# df2_redraw.net
KiCad netlist of a schematic drawn in EAGLE
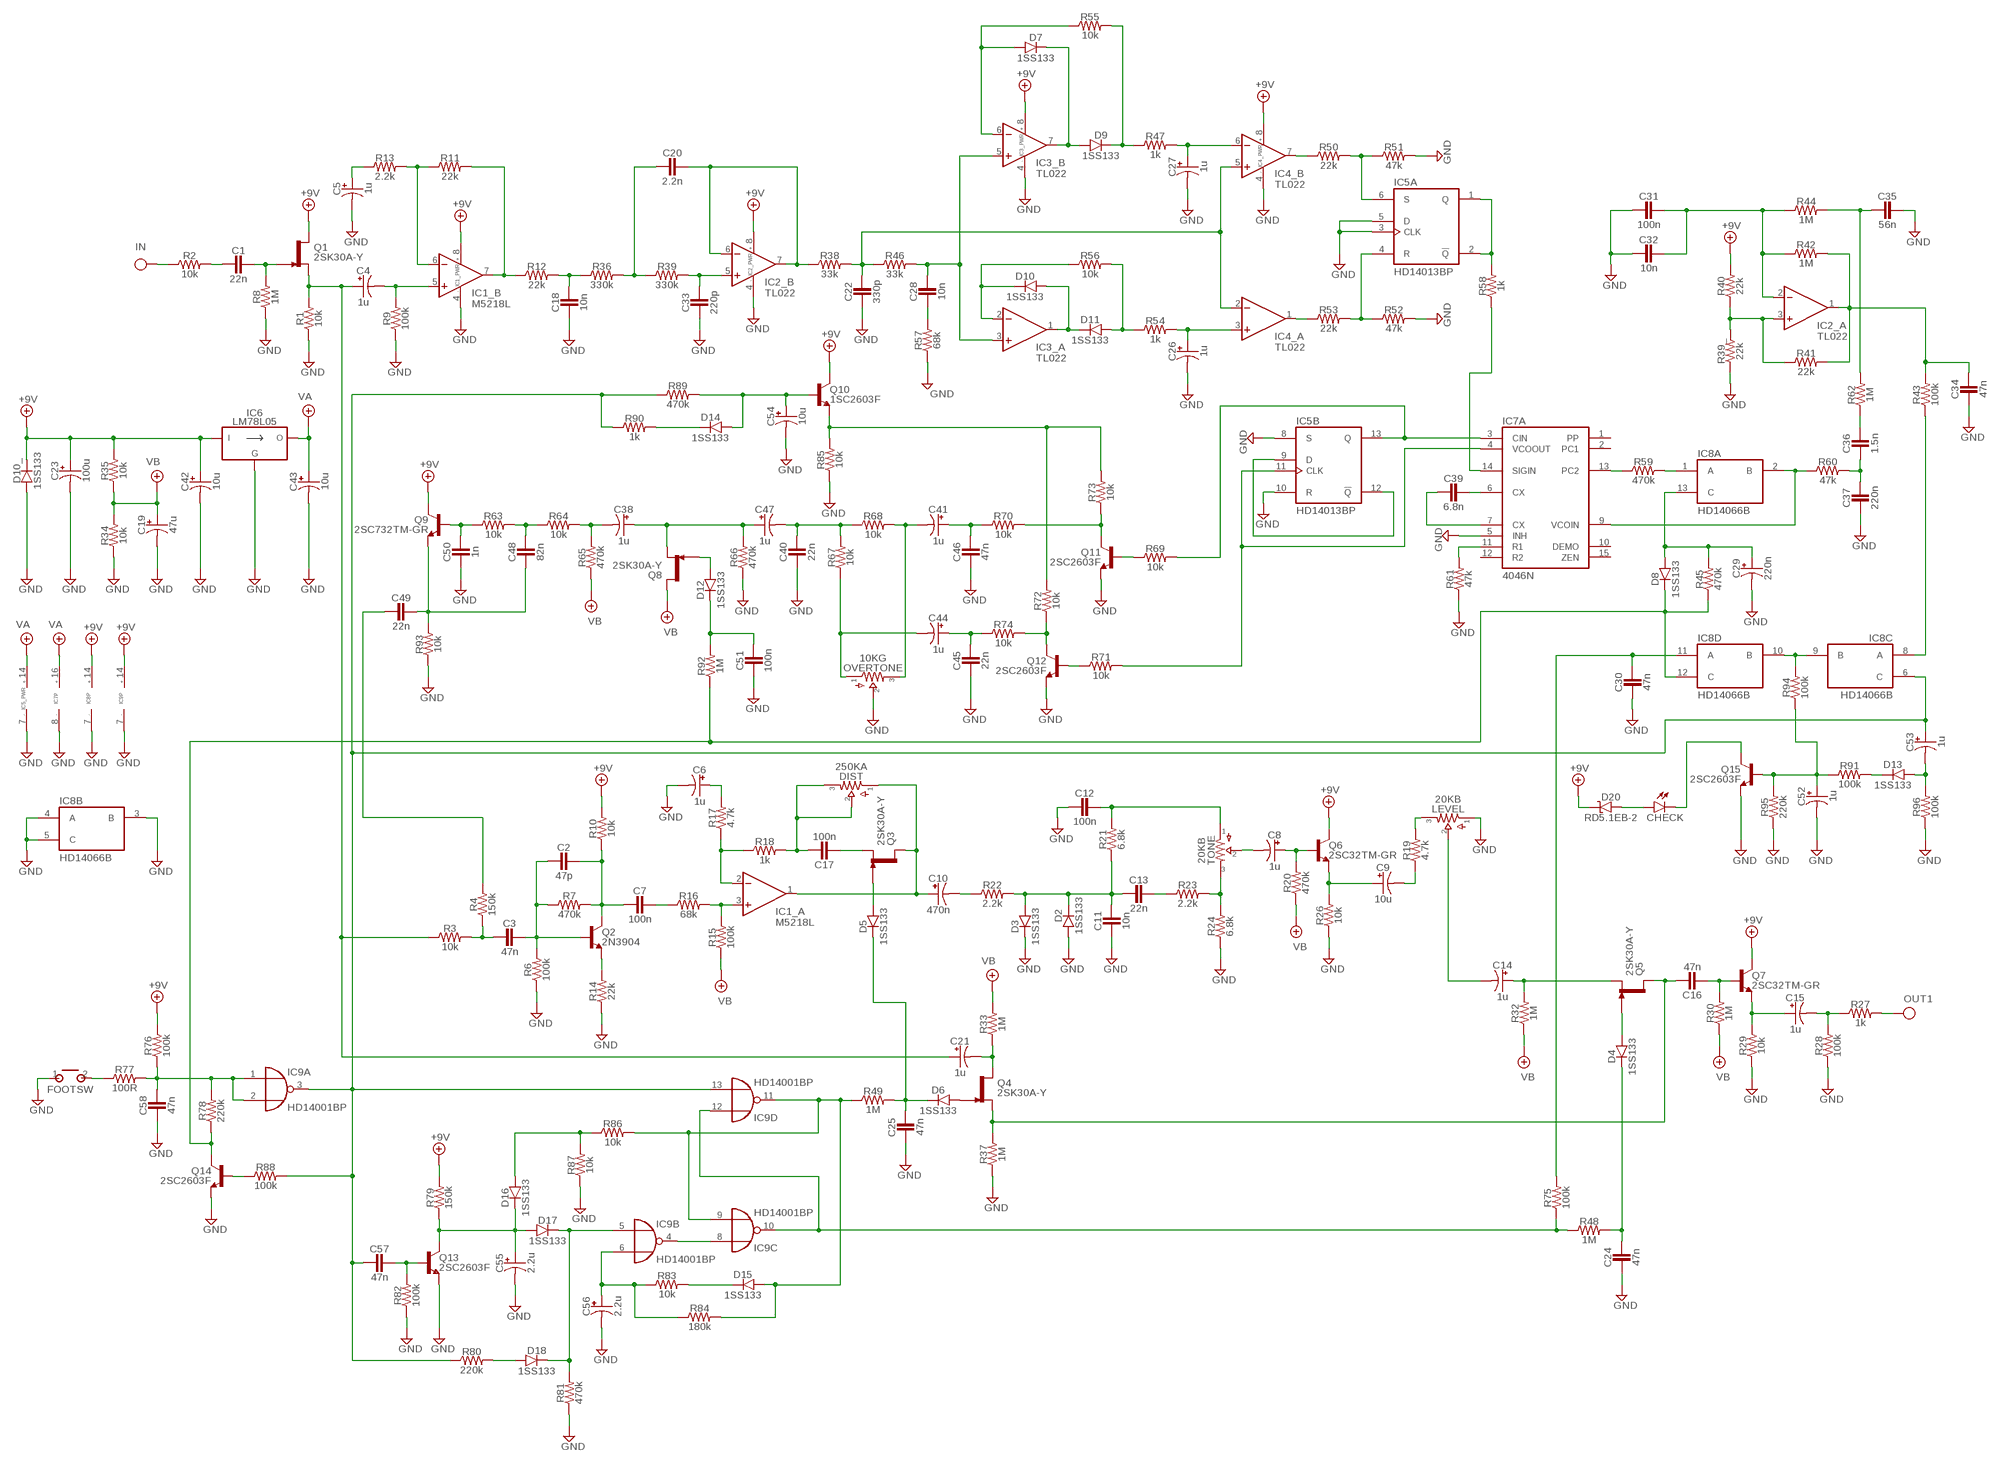
[diagram p0: schematic, sheet 1]

(export (version "E")
  (design (tool "Eeschema 10.0.6"))
  (components
    (comp (ref "C1")
      (value "22n")
      (footprint "eagle-import:BOX_SMALL")
      (libsource (lib "eagle-import") (part "CER/FILMBOX.1"))
    )
    (comp (ref "C2")
      (value "47p")
      (footprint "eagle-import:BOX_SMALL")
      (libsource (lib "eagle-import") (part "CER/FILMBOX.1"))
    )
    (comp (ref "C3")
      (value "47n")
      (footprint "eagle-import:BOX_SMALL")
      (libsource (lib "eagle-import") (part "CER/FILMBOX.1"))
    )
    (comp (ref "C4")
      (value "1u")
      (footprint "eagle-import:040_020")
      (libsource (lib "eagle-import") (part "0400"))
    )
    (comp (ref "C5")
      (value "1u")
      (footprint "eagle-import:040_020")
      (libsource (lib "eagle-import") (part "0400"))
    )
    (comp (ref "C6")
      (value "1u")
      (footprint "eagle-import:040_020")
      (libsource (lib "eagle-import") (part "0400"))
    )
    (comp (ref "C7")
      (value "100n")
      (footprint "eagle-import:BOX_SMALL")
      (libsource (lib "eagle-import") (part "CER/FILMBOX.1"))
    )
    (comp (ref "C8")
      (value "1u")
      (footprint "eagle-import:040_020")
      (libsource (lib "eagle-import") (part "0400"))
    )
    (comp (ref "C9")
      (value "10u")
      (footprint "eagle-import:040_020")
      (libsource (lib "eagle-import") (part "0400"))
    )
    (comp (ref "C10")
      (value "470n")
      (footprint "eagle-import:040_020")
      (libsource (lib "eagle-import") (part "0400"))
    )
    (comp (ref "C11")
      (value "10n")
      (footprint "eagle-import:BOX_SMALL")
      (libsource (lib "eagle-import") (part "CER/FILMBOX.1"))
    )
    (comp (ref "C12")
      (value "100n")
      (footprint "eagle-import:BOX_SMALL")
      (libsource (lib "eagle-import") (part "CER/FILMBOX.1"))
    )
    (comp (ref "C13")
      (value "22n")
      (footprint "eagle-import:BOX_SMALL")
      (libsource (lib "eagle-import") (part "CER/FILMBOX.1"))
    )
    (comp (ref "C14")
      (value "1u")
      (footprint "eagle-import:040_020")
      (libsource (lib "eagle-import") (part "0400"))
    )
    (comp (ref "C15")
      (value "1u")
      (footprint "eagle-import:040_020")
      (libsource (lib "eagle-import") (part "0400"))
    )
    (comp (ref "C16")
      (value "47n")
      (footprint "eagle-import:BOX_SMALL")
      (libsource (lib "eagle-import") (part "CER/FILMBOX.1"))
    )
    (comp (ref "C17")
      (value "100n")
      (footprint "eagle-import:BOX_SMALL")
      (libsource (lib "eagle-import") (part "CER/FILMBOX.1"))
    )
    (comp (ref "C18")
      (value "10n")
      (footprint "eagle-import:BOX_SMALL")
      (libsource (lib "eagle-import") (part "CER/FILMBOX.1"))
    )
    (comp (ref "C19")
      (value "47u")
      (footprint "eagle-import:040_020")
      (libsource (lib "eagle-import") (part "0400"))
    )
    (comp (ref "C20")
      (value "2.2n")
      (footprint "eagle-import:BOX_SMALL")
      (libsource (lib "eagle-import") (part "CER/FILMBOX.1"))
    )
    (comp (ref "C21")
      (value "1u")
      (footprint "eagle-import:040_020")
      (libsource (lib "eagle-import") (part "0400"))
    )
    (comp (ref "C22")
      (value "330p")
      (footprint "eagle-import:BOX_SMALL")
      (libsource (lib "eagle-import") (part "CER/FILMBOX.1"))
    )
    (comp (ref "C23")
      (value "100u")
      (footprint "eagle-import:040_020")
      (libsource (lib "eagle-import") (part "0400"))
    )
    (comp (ref "C24")
      (value "47n")
      (footprint "eagle-import:BOX_SMALL")
      (libsource (lib "eagle-import") (part "CER/FILMBOX.1"))
    )
    (comp (ref "C25")
      (value "47n")
      (footprint "eagle-import:BOX_SMALL")
      (libsource (lib "eagle-import") (part "CER/FILMBOX.1"))
    )
    (comp (ref "C26")
      (value "1u")
      (footprint "eagle-import:040_020")
      (libsource (lib "eagle-import") (part "0400"))
    )
    (comp (ref "C27")
      (value "1u")
      (footprint "eagle-import:040_020")
      (libsource (lib "eagle-import") (part "0400"))
    )
    (comp (ref "C28")
      (value "10n")
      (footprint "eagle-import:BOX_SMALL")
      (libsource (lib "eagle-import") (part "CER/FILMBOX.1"))
    )
    (comp (ref "C29")
      (value "220n")
      (footprint "eagle-import:040_020")
      (libsource (lib "eagle-import") (part "0400"))
    )
    (comp (ref "C30")
      (value "47n")
      (footprint "eagle-import:BOX_SMALL")
      (libsource (lib "eagle-import") (part "CER/FILMBOX.1"))
    )
    (comp (ref "C31")
      (value "100n")
      (footprint "eagle-import:BOX_SMALL")
      (libsource (lib "eagle-import") (part "CER/FILMBOX.1"))
    )
    (comp (ref "C32")
      (value "10n")
      (footprint "eagle-import:BOX_SMALL")
      (libsource (lib "eagle-import") (part "CER/FILMBOX.1"))
    )
    (comp (ref "C33")
      (value "220p")
      (footprint "eagle-import:BOX_SMALL")
      (libsource (lib "eagle-import") (part "CER/FILMBOX.1"))
    )
    (comp (ref "C34")
      (value "47n")
      (footprint "eagle-import:BOX_SMALL")
      (libsource (lib "eagle-import") (part "CER/FILMBOX.1"))
    )
    (comp (ref "C35")
      (value "56n")
      (footprint "eagle-import:BOX_SMALL")
      (libsource (lib "eagle-import") (part "CER/FILMBOX.1"))
    )
    (comp (ref "C36")
      (value "1.5n")
      (footprint "eagle-import:BOX_SMALL")
      (libsource (lib "eagle-import") (part "CER/FILMBOX.1"))
    )
    (comp (ref "C37")
      (value "220n")
      (footprint "eagle-import:BOX_SMALL")
      (libsource (lib "eagle-import") (part "CER/FILMBOX.1"))
    )
    (comp (ref "C38")
      (value "1u")
      (footprint "eagle-import:040_020")
      (libsource (lib "eagle-import") (part "0400"))
    )
    (comp (ref "C39")
      (value "6.8n")
      (footprint "eagle-import:BOX_SMALL")
      (libsource (lib "eagle-import") (part "CER/FILMBOX.1"))
    )
    (comp (ref "C40")
      (value "22n")
      (footprint "eagle-import:BOX_SMALL")
      (libsource (lib "eagle-import") (part "CER/FILMBOX.1"))
    )
    (comp (ref "C41")
      (value "1u")
      (footprint "eagle-import:040_020")
      (libsource (lib "eagle-import") (part "0400"))
    )
    (comp (ref "C42")
      (value "10u")
      (footprint "eagle-import:040_020")
      (libsource (lib "eagle-import") (part "0400"))
    )
    (comp (ref "C43")
      (value "10u")
      (footprint "eagle-import:040_020")
      (libsource (lib "eagle-import") (part "0400"))
    )
    (comp (ref "C44")
      (value "1u")
      (footprint "eagle-import:040_020")
      (libsource (lib "eagle-import") (part "0400"))
    )
    (comp (ref "C45")
      (value "22n")
      (footprint "eagle-import:BOX_SMALL")
      (libsource (lib "eagle-import") (part "CER/FILMBOX.1"))
    )
    (comp (ref "C46")
      (value "47n")
      (footprint "eagle-import:BOX_SMALL")
      (libsource (lib "eagle-import") (part "CER/FILMBOX.1"))
    )
    (comp (ref "C47")
      (value "1u")
      (footprint "eagle-import:040_020")
      (libsource (lib "eagle-import") (part "0400"))
    )
    (comp (ref "C48")
      (value "82n")
      (footprint "eagle-import:BOX_SMALL")
      (libsource (lib "eagle-import") (part "CER/FILMBOX.1"))
    )
    (comp (ref "C49")
      (value "22n")
      (footprint "eagle-import:BOX_SMALL")
      (libsource (lib "eagle-import") (part "CER/FILMBOX.1"))
    )
    (comp (ref "C50")
      (value "1n")
      (footprint "eagle-import:BOX_SMALL")
      (libsource (lib "eagle-import") (part "CER/FILMBOX.1"))
    )
    (comp (ref "C51")
      (value "100n")
      (footprint "eagle-import:BOX_SMALL")
      (libsource (lib "eagle-import") (part "CER/FILMBOX.1"))
    )
    (comp (ref "C52")
      (value "1u")
      (footprint "eagle-import:040_020")
      (libsource (lib "eagle-import") (part "0400"))
    )
    (comp (ref "C53")
      (value "1u")
      (footprint "eagle-import:040_020")
      (libsource (lib "eagle-import") (part "0400"))
    )
    (comp (ref "C54")
      (value "10u")
      (footprint "eagle-import:040_020")
      (libsource (lib "eagle-import") (part "0400"))
    )
    (comp (ref "C55")
      (value "2.2u")
      (footprint "eagle-import:040_020")
      (libsource (lib "eagle-import") (part "0400"))
    )
    (comp (ref "C56")
      (value "2.2u")
      (footprint "eagle-import:040_020")
      (libsource (lib "eagle-import") (part "0400"))
    )
    (comp (ref "C57")
      (value "47n")
      (footprint "eagle-import:BOX_SMALL")
      (libsource (lib "eagle-import") (part "CER/FILMBOX.1"))
    )
    (comp (ref "C58")
      (value "47n")
      (footprint "eagle-import:BOX_SMALL")
      (libsource (lib "eagle-import") (part "CER/FILMBOX.1"))
    )
    (comp (ref "CHECK")
      (value "LED")
      (footprint "eagle-import:3MM_D")
      (libsource (lib "eagle-import") (part "LED"))
    )
    (comp (ref "D2")
      (value "1SS133")
      (footprint "eagle-import:DO35-2")
      (libsource (lib "eagle-import") (part "DO35.2"))
    )
    (comp (ref "D3")
      (value "1SS133")
      (footprint "eagle-import:DO35-2")
      (libsource (lib "eagle-import") (part "DO35.2"))
    )
    (comp (ref "D4")
      (value "1SS133")
      (footprint "eagle-import:DO35-2")
      (libsource (lib "eagle-import") (part "DO35.2"))
    )
    (comp (ref "D5")
      (value "1SS133")
      (footprint "eagle-import:DO35-2")
      (libsource (lib "eagle-import") (part "DO35.2"))
    )
    (comp (ref "D6")
      (value "1SS133")
      (footprint "eagle-import:DO35-2")
      (libsource (lib "eagle-import") (part "DO35.2"))
    )
    (comp (ref "D7")
      (value "1SS133")
      (footprint "eagle-import:DO35-2")
      (libsource (lib "eagle-import") (part "DO35.2"))
    )
    (comp (ref "D8")
      (value "1SS133")
      (footprint "eagle-import:DO35-2")
      (libsource (lib "eagle-import") (part "DO35.2"))
    )
    (comp (ref "D9")
      (value "1SS133")
      (footprint "eagle-import:DO35-2")
      (libsource (lib "eagle-import") (part "DO35.2"))
    )
    (comp (ref "D10")
      (value "1SS133")
      (footprint "eagle-import:DO35-2")
      (libsource (lib "eagle-import") (part "DO35.2"))
    )
    (comp (ref "D10_")
      (value "1SS133")
      (footprint "eagle-import:DO35-2")
      (libsource (lib "eagle-import") (part "DO35.2"))
    )
    (comp (ref "D11")
      (value "1SS133")
      (footprint "eagle-import:DO35-2")
      (libsource (lib "eagle-import") (part "DO35.2"))
    )
    (comp (ref "D12")
      (value "1SS133")
      (footprint "eagle-import:DO35-2")
      (libsource (lib "eagle-import") (part "DO35.2"))
    )
    (comp (ref "D13")
      (value "1SS133")
      (footprint "eagle-import:DO35-2")
      (libsource (lib "eagle-import") (part "DO35.2"))
    )
    (comp (ref "D14")
      (value "1SS133")
      (footprint "eagle-import:DO35-2")
      (libsource (lib "eagle-import") (part "DO35.2"))
    )
    (comp (ref "D15")
      (value "1SS133")
      (footprint "eagle-import:DO35-2")
      (libsource (lib "eagle-import") (part "DO35.2"))
    )
    (comp (ref "D16")
      (value "1SS133")
      (footprint "eagle-import:DO35-2")
      (libsource (lib "eagle-import") (part "DO35.2"))
    )
    (comp (ref "D17")
      (value "1SS133")
      (footprint "eagle-import:DO35-2")
      (libsource (lib "eagle-import") (part "DO35.2"))
    )
    (comp (ref "D18")
      (value "1SS133")
      (footprint "eagle-import:DO35-2")
      (libsource (lib "eagle-import") (part "DO35.2"))
    )
    (comp (ref "D20")
      (value "RD5.1EB-2")
      (footprint "eagle-import:DO41-2")
      (libsource (lib "eagle-import") (part "ZENER.2"))
    )
    (comp (ref "DIST")
      (value "250KA")
      (footprint "eagle-import:16MM_CENTERMOUNT")
      (libsource (lib "eagle-import") (part "POTS"))
    )
    (comp (ref "FOOTSW")
      (value "MOMENTARY")
      (footprint "eagle-import:SPST")
      (libsource (lib "eagle-import") (part "MOMENTARY"))
    )
    (comp (ref "IC1")
      (value "M5218L")
      (footprint "eagle-import:DIL0")
      (libsource (lib "eagle-import") (part "DUALTH"))
    )
    (comp (ref "IC2")
      (value "TL022")
      (footprint "eagle-import:DIL0")
      (libsource (lib "eagle-import") (part "DUALTH"))
    )
    (comp (ref "IC3")
      (value "TL022")
      (footprint "eagle-import:DIL0")
      (libsource (lib "eagle-import") (part "DUALTH"))
    )
    (comp (ref "IC4")
      (value "TL022")
      (footprint "eagle-import:DIL0")
      (libsource (lib "eagle-import") (part "DUALTH"))
    )
    (comp (ref "IC5")
      (value "HD14013BP")
      (footprint "eagle-import:DIL14")
      (libsource (lib "eagle-import") (part "4013N"))
    )
    (comp (ref "IC6")
      (value "LM78L05")
      (footprint "eagle-import:TO92-")
      (libsource (lib "eagle-import") (part "LM78L05"))
    )
    (comp (ref "IC7")
      (value "4046N")
      (footprint "eagle-import:DIL16")
      (libsource (lib "eagle-import") (part "4046N"))
    )
    (comp (ref "IC8")
      (value "HD14066B")
      (footprint "eagle-import:DIL14")
      (libsource (lib "eagle-import") (part "4066N"))
    )
    (comp (ref "IC9")
      (value "HD14001BP")
      (footprint "eagle-import:DIL14")
      (libsource (lib "eagle-import") (part "4001N"))
    )
    (comp (ref "LEVEL")
      (value "20KB")
      (footprint "eagle-import:16MM_CENTERMOUNT")
      (libsource (lib "eagle-import") (part "POTS"))
    )
    (comp (ref "OVERTONE")
      (value "10KG")
      (footprint "eagle-import:16MM_CENTERMOUNT")
      (libsource (lib "eagle-import") (part "POTS"))
    )
    (comp (ref "Q1")
      (value "2SK30A-Y")
      (footprint "eagle-import:TO92-")
      (libsource (lib "eagle-import") (part "2SK30A"))
    )
    (comp (ref "Q2")
      (value "2N3904")
      (footprint "eagle-import:TO92-")
      (libsource (lib "eagle-import") (part "2N3904"))
    )
    (comp (ref "Q3")
      (value "2SK30A-Y")
      (footprint "eagle-import:TO92-")
      (libsource (lib "eagle-import") (part "2SK30A"))
    )
    (comp (ref "Q4")
      (value "2SK30A-Y")
      (footprint "eagle-import:TO92-")
      (libsource (lib "eagle-import") (part "2SK30A"))
    )
    (comp (ref "Q5")
      (value "2SK30A-Y")
      (footprint "eagle-import:TO92-")
      (libsource (lib "eagle-import") (part "2SK30A"))
    )
    (comp (ref "Q6")
      (value "2SC32TM-GR")
      (footprint "eagle-import:TO92-")
      (libsource (lib "eagle-import") (part "2N3904"))
    )
    (comp (ref "Q7")
      (value "2SC32TM-GR")
      (footprint "eagle-import:TO92-")
      (libsource (lib "eagle-import") (part "2N3904"))
    )
    (comp (ref "Q8")
      (value "2SK30A-Y")
      (footprint "eagle-import:TO92-")
      (libsource (lib "eagle-import") (part "2SK30A"))
    )
    (comp (ref "Q9")
      (value "2SC732TM-GR")
      (footprint "eagle-import:TO92-")
      (libsource (lib "eagle-import") (part "2N3904"))
    )
    (comp (ref "Q10")
      (value "1SC2603F")
      (footprint "eagle-import:TO92-")
      (libsource (lib "eagle-import") (part "2N3904"))
    )
    (comp (ref "Q11")
      (value "2SC2603F")
      (footprint "eagle-import:TO92-")
      (libsource (lib "eagle-import") (part "2N3904"))
    )
    (comp (ref "Q12")
      (value "2SC2603F")
      (footprint "eagle-import:TO92-")
      (libsource (lib "eagle-import") (part "2N3904"))
    )
    (comp (ref "Q13")
      (value "2SC2603F")
      (footprint "eagle-import:TO92-")
      (libsource (lib "eagle-import") (part "2N3904"))
    )
    (comp (ref "Q14")
      (value "2SC2603F")
      (footprint "eagle-import:TO92-")
      (libsource (lib "eagle-import") (part "2N3904"))
    )
    (comp (ref "Q15")
      (value "2SC2603F")
      (footprint "eagle-import:TO92-")
      (libsource (lib "eagle-import") (part "2N3904"))
    )
    (comp (ref "R1")
      (value "10k")
      (footprint "eagle-import:R0207_3")
      (libsource (lib "eagle-import") (part "R_.3B"))
    )
    (comp (ref "R2")
      (value "10k")
      (footprint "eagle-import:R0207_3")
      (libsource (lib "eagle-import") (part "R_.3B"))
    )
    (comp (ref "R3")
      (value "10k")
      (footprint "eagle-import:R0207_3")
      (libsource (lib "eagle-import") (part "R_.3B"))
    )
    (comp (ref "R4")
      (value "150k")
      (footprint "eagle-import:R0207_3")
      (libsource (lib "eagle-import") (part "R_.3B"))
    )
    (comp (ref "R6")
      (value "100k")
      (footprint "eagle-import:R0207_3")
      (libsource (lib "eagle-import") (part "R_.3B"))
    )
    (comp (ref "R7")
      (value "470k")
      (footprint "eagle-import:R0207_3")
      (libsource (lib "eagle-import") (part "R_.3B"))
    )
    (comp (ref "R8")
      (value "1M")
      (footprint "eagle-import:R0207_3")
      (libsource (lib "eagle-import") (part "R_.3B"))
    )
    (comp (ref "R9")
      (value "100k")
      (footprint "eagle-import:R0207_3")
      (libsource (lib "eagle-import") (part "R_.3B"))
    )
    (comp (ref "R10")
      (value "10k")
      (footprint "eagle-import:R0207_3")
      (libsource (lib "eagle-import") (part "R_.3B"))
    )
    (comp (ref "R11")
      (value "22k")
      (footprint "eagle-import:R0207_3")
      (libsource (lib "eagle-import") (part "R_.3B"))
    )
    (comp (ref "R12")
      (value "22k")
      (footprint "eagle-import:R0207_3")
      (libsource (lib "eagle-import") (part "R_.3B"))
    )
    (comp (ref "R13")
      (value "2.2k")
      (footprint "eagle-import:R0207_3")
      (libsource (lib "eagle-import") (part "R_.3B"))
    )
    (comp (ref "R14")
      (value "22k")
      (footprint "eagle-import:R0207_3")
      (libsource (lib "eagle-import") (part "R_.3B"))
    )
    (comp (ref "R15")
      (value "100k")
      (footprint "eagle-import:R0207_3")
      (libsource (lib "eagle-import") (part "R_.3B"))
    )
    (comp (ref "R16")
      (value "68k")
      (footprint "eagle-import:R0207_3")
      (libsource (lib "eagle-import") (part "R_.3B"))
    )
    (comp (ref "R17")
      (value "4.7k")
      (footprint "eagle-import:R0207_3")
      (libsource (lib "eagle-import") (part "R_.3B"))
    )
    (comp (ref "R18")
      (value "1k")
      (footprint "eagle-import:R0207_3")
      (libsource (lib "eagle-import") (part "R_.3B"))
    )
    (comp (ref "R19")
      (value "4.7k")
      (footprint "eagle-import:R0207_3")
      (libsource (lib "eagle-import") (part "R_.3B"))
    )
    (comp (ref "R20")
      (value "470k")
      (footprint "eagle-import:R0207_3")
      (libsource (lib "eagle-import") (part "R_.3B"))
    )
    (comp (ref "R21")
      (value "6.8k")
      (footprint "eagle-import:R0207_3")
      (libsource (lib "eagle-import") (part "R_.3B"))
    )
    (comp (ref "R22")
      (value "2.2k")
      (footprint "eagle-import:R0207_3")
      (libsource (lib "eagle-import") (part "R_.3B"))
    )
    (comp (ref "R23")
      (value "2.2k")
      (footprint "eagle-import:R0207_3")
      (libsource (lib "eagle-import") (part "R_.3B"))
    )
    (comp (ref "R24")
      (value "6.8k")
      (footprint "eagle-import:R0207_3")
      (libsource (lib "eagle-import") (part "R_.3B"))
    )
    (comp (ref "R26")
      (value "10k")
      (footprint "eagle-import:R0207_3")
      (libsource (lib "eagle-import") (part "R_.3B"))
    )
    (comp (ref "R27")
      (value "1k")
      (footprint "eagle-import:R0207_3")
      (libsource (lib "eagle-import") (part "R_.3B"))
    )
    (comp (ref "R28")
      (value "100k")
      (footprint "eagle-import:R0207_3")
      (libsource (lib "eagle-import") (part "R_.3B"))
    )
    (comp (ref "R29")
      (value "10k")
      (footprint "eagle-import:R0207_3")
      (libsource (lib "eagle-import") (part "R_.3B"))
    )
    (comp (ref "R30")
      (value "1M")
      (footprint "eagle-import:R0207_3")
      (libsource (lib "eagle-import") (part "R_.3B"))
    )
    (comp (ref "R32")
      (value "1M")
      (footprint "eagle-import:R0207_3")
      (libsource (lib "eagle-import") (part "R_.3B"))
    )
    (comp (ref "R33")
      (value "1M")
      (footprint "eagle-import:R0207_3")
      (libsource (lib "eagle-import") (part "R_.3B"))
    )
    (comp (ref "R34")
      (value "10k")
      (footprint "eagle-import:R0207_3")
      (libsource (lib "eagle-import") (part "R_.3B"))
    )
    (comp (ref "R35")
      (value "10k")
      (footprint "eagle-import:R0207_3")
      (libsource (lib "eagle-import") (part "R_.3B"))
    )
    (comp (ref "R36")
      (value "330k")
      (footprint "eagle-import:R0207_3")
      (libsource (lib "eagle-import") (part "R_.3B"))
    )
    (comp (ref "R37")
      (value "1M")
      (footprint "eagle-import:R0207_3")
      (libsource (lib "eagle-import") (part "R_.3B"))
    )
    (comp (ref "R38")
      (value "33k")
      (footprint "eagle-import:R0207_3")
      (libsource (lib "eagle-import") (part "R_.3B"))
    )
    (comp (ref "R39")
      (value "330k")
      (footprint "eagle-import:R0207_3")
      (libsource (lib "eagle-import") (part "R_.3B"))
    )
    (comp (ref "R39_")
      (value "22k")
      (footprint "eagle-import:R0207_3")
      (libsource (lib "eagle-import") (part "R_.3B"))
    )
    (comp (ref "R40")
      (value "22k")
      (footprint "eagle-import:R0207_3")
      (libsource (lib "eagle-import") (part "R_.3B"))
    )
    (comp (ref "R41")
      (value "22k")
      (footprint "eagle-import:R0207_3")
      (libsource (lib "eagle-import") (part "R_.3B"))
    )
    (comp (ref "R42")
      (value "1M")
      (footprint "eagle-import:R0207_3")
      (libsource (lib "eagle-import") (part "R_.3B"))
    )
    (comp (ref "R43")
      (value "100k")
      (footprint "eagle-import:R0207_3")
      (libsource (lib "eagle-import") (part "R_.3B"))
    )
    (comp (ref "R44")
      (value "1M")
      (footprint "eagle-import:R0207_3")
      (libsource (lib "eagle-import") (part "R_.3B"))
    )
    (comp (ref "R45")
      (value "470k")
      (footprint "eagle-import:R0207_3")
      (libsource (lib "eagle-import") (part "R_.3B"))
    )
    (comp (ref "R46")
      (value "33k")
      (footprint "eagle-import:R0207_3")
      (libsource (lib "eagle-import") (part "R_.3B"))
    )
    (comp (ref "R47")
      (value "1k")
      (footprint "eagle-import:R0207_3")
      (libsource (lib "eagle-import") (part "R_.3B"))
    )
    (comp (ref "R48")
      (value "1M")
      (footprint "eagle-import:R0207_3")
      (libsource (lib "eagle-import") (part "R_.3B"))
    )
    (comp (ref "R49")
      (value "1M")
      (footprint "eagle-import:R0207_3")
      (libsource (lib "eagle-import") (part "R_.3B"))
    )
    (comp (ref "R50")
      (value "22k")
      (footprint "eagle-import:R0207_3")
      (libsource (lib "eagle-import") (part "R_.3B"))
    )
    (comp (ref "R51")
      (value "47k")
      (footprint "eagle-import:R0207_3")
      (libsource (lib "eagle-import") (part "R_.3B"))
    )
    (comp (ref "R52")
      (value "47k")
      (footprint "eagle-import:R0207_3")
      (libsource (lib "eagle-import") (part "R_.3B"))
    )
    (comp (ref "R53")
      (value "22k")
      (footprint "eagle-import:R0207_3")
      (libsource (lib "eagle-import") (part "R_.3B"))
    )
    (comp (ref "R54")
      (value "1k")
      (footprint "eagle-import:R0207_3")
      (libsource (lib "eagle-import") (part "R_.3B"))
    )
    (comp (ref "R55")
      (value "10k")
      (footprint "eagle-import:R0207_3")
      (libsource (lib "eagle-import") (part "R_.3B"))
    )
    (comp (ref "R56")
      (value "10k")
      (footprint "eagle-import:R0207_3")
      (libsource (lib "eagle-import") (part "R_.3B"))
    )
    (comp (ref "R57")
      (value "68k")
      (footprint "eagle-import:R0207_3")
      (libsource (lib "eagle-import") (part "R_.3B"))
    )
    (comp (ref "R58")
      (value "1k")
      (footprint "eagle-import:R0207_3")
      (libsource (lib "eagle-import") (part "R_.3B"))
    )
    (comp (ref "R59")
      (value "470k")
      (footprint "eagle-import:R0207_3")
      (libsource (lib "eagle-import") (part "R_.3B"))
    )
    (comp (ref "R60")
      (value "47k")
      (footprint "eagle-import:R0207_3")
      (libsource (lib "eagle-import") (part "R_.3B"))
    )
    (comp (ref "R61")
      (value "47k")
      (footprint "eagle-import:R0207_3")
      (libsource (lib "eagle-import") (part "R_.3B"))
    )
    (comp (ref "R62")
      (value "1M")
      (footprint "eagle-import:R0207_3")
      (libsource (lib "eagle-import") (part "R_.3B"))
    )
    (comp (ref "R63")
      (value "10k")
      (footprint "eagle-import:R0207_3")
      (libsource (lib "eagle-import") (part "R_.3B"))
    )
    (comp (ref "R64")
      (value "10k")
      (footprint "eagle-import:R0207_3")
      (libsource (lib "eagle-import") (part "R_.3B"))
    )
    (comp (ref "R65")
      (value "470k")
      (footprint "eagle-import:R0207_3")
      (libsource (lib "eagle-import") (part "R_.3B"))
    )
    (comp (ref "R66")
      (value "470k")
      (footprint "eagle-import:R0207_3")
      (libsource (lib "eagle-import") (part "R_.3B"))
    )
    (comp (ref "R67")
      (value "10k")
      (footprint "eagle-import:R0207_3")
      (libsource (lib "eagle-import") (part "R_.3B"))
    )
    (comp (ref "R68")
      (value "10k")
      (footprint "eagle-import:R0207_3")
      (libsource (lib "eagle-import") (part "R_.3B"))
    )
    (comp (ref "R69")
      (value "10k")
      (footprint "eagle-import:R0207_3")
      (libsource (lib "eagle-import") (part "R_.3B"))
    )
    (comp (ref "R70")
      (value "10k")
      (footprint "eagle-import:R0207_3")
      (libsource (lib "eagle-import") (part "R_.3B"))
    )
    (comp (ref "R71")
      (value "10k")
      (footprint "eagle-import:R0207_3")
      (libsource (lib "eagle-import") (part "R_.3B"))
    )
    (comp (ref "R72")
      (value "10k")
      (footprint "eagle-import:R0207_3")
      (libsource (lib "eagle-import") (part "R_.3B"))
    )
    (comp (ref "R73")
      (value "10k")
      (footprint "eagle-import:R0207_3")
      (libsource (lib "eagle-import") (part "R_.3B"))
    )
    (comp (ref "R74")
      (value "10k")
      (footprint "eagle-import:R0207_3")
      (libsource (lib "eagle-import") (part "R_.3B"))
    )
    (comp (ref "R75")
      (value "100k")
      (footprint "eagle-import:R0207_3")
      (libsource (lib "eagle-import") (part "R_.3B"))
    )
    (comp (ref "R76")
      (value "100k")
      (footprint "eagle-import:R0207_3")
      (libsource (lib "eagle-import") (part "R_.3B"))
    )
    (comp (ref "R77")
      (value "100R")
      (footprint "eagle-import:R0207_3")
      (libsource (lib "eagle-import") (part "R_.3B"))
    )
    (comp (ref "R78")
      (value "220k")
      (footprint "eagle-import:R0207_3")
      (libsource (lib "eagle-import") (part "R_.3B"))
    )
    (comp (ref "R79")
      (value "150k")
      (footprint "eagle-import:R0207_3")
      (libsource (lib "eagle-import") (part "R_.3B"))
    )
    (comp (ref "R80")
      (value "220k")
      (footprint "eagle-import:R0207_3")
      (libsource (lib "eagle-import") (part "R_.3B"))
    )
    (comp (ref "R81")
      (value "470k")
      (footprint "eagle-import:R0207_3")
      (libsource (lib "eagle-import") (part "R_.3B"))
    )
    (comp (ref "R82")
      (value "100k")
      (footprint "eagle-import:R0207_3")
      (libsource (lib "eagle-import") (part "R_.3B"))
    )
    (comp (ref "R83")
      (value "10k")
      (footprint "eagle-import:R0207_3")
      (libsource (lib "eagle-import") (part "R_.3B"))
    )
    (comp (ref "R84")
      (value "180k")
      (footprint "eagle-import:R0207_3")
      (libsource (lib "eagle-import") (part "R_.3B"))
    )
    (comp (ref "R85")
      (value "10k")
      (footprint "eagle-import:R0207_3")
      (libsource (lib "eagle-import") (part "R_.3B"))
    )
    (comp (ref "R86")
      (value "10k")
      (footprint "eagle-import:R0207_3")
      (libsource (lib "eagle-import") (part "R_.3B"))
    )
    (comp (ref "R87")
      (value "10k")
      (footprint "eagle-import:R0207_3")
      (libsource (lib "eagle-import") (part "R_.3B"))
    )
    (comp (ref "R88")
      (value "100k")
      (footprint "eagle-import:R0207_3")
      (libsource (lib "eagle-import") (part "R_.3B"))
    )
    (comp (ref "R89")
      (value "470k")
      (footprint "eagle-import:R0207_3")
      (libsource (lib "eagle-import") (part "R_.3B"))
    )
    (comp (ref "R90")
      (value "1k")
      (footprint "eagle-import:R0207_3")
      (libsource (lib "eagle-import") (part "R_.3B"))
    )
    (comp (ref "R91")
      (value "100k")
      (footprint "eagle-import:R0207_3")
      (libsource (lib "eagle-import") (part "R_.3B"))
    )
    (comp (ref "R92")
      (value "1M")
      (footprint "eagle-import:R0207_3")
      (libsource (lib "eagle-import") (part "R_.3B"))
    )
    (comp (ref "R93")
      (value "10k")
      (footprint "eagle-import:R0207_3")
      (libsource (lib "eagle-import") (part "R_.3B"))
    )
    (comp (ref "R94")
      (value "100k")
      (footprint "eagle-import:R0207_3")
      (libsource (lib "eagle-import") (part "R_.3B"))
    )
    (comp (ref "R95")
      (value "220k")
      (footprint "eagle-import:R0207_3")
      (libsource (lib "eagle-import") (part "R_.3B"))
    )
    (comp (ref "R96")
      (value "100k")
      (footprint "eagle-import:R0207_3")
      (libsource (lib "eagle-import") (part "R_.3B"))
    )
    (comp (ref "TONE")
      (value "20KB")
      (footprint "eagle-import:16MM_CENTERMOUNT")
      (libsource (lib "eagle-import") (part "POTS"))
    )
  )
  (nets
    (net (code "1") (name "+9V") (class "Default")
      (node (ref "C23") (pin "+") (pinfunction "+_+") (pintype "passive"))
      (node (ref "C42") (pin "+") (pinfunction "+_+") (pintype "passive"))
      (node (ref "D10_") (pin "C") (pinfunction "C_C") (pintype "passive"))
      (node (ref "D20") (pin "C") (pinfunction "C_C") (pintype "passive"))
      (node (ref "IC1") (pin "8") (pinfunction "V+_8") (pintype "power_in"))
      (node (ref "IC2") (pin "8") (pinfunction "V+_8") (pintype "power_in"))
      (node (ref "IC3") (pin "8") (pinfunction "V+_8") (pintype "power_in"))
      (node (ref "IC4") (pin "8") (pinfunction "V+_8") (pintype "power_in"))
      (node (ref "IC6") (pin "1") (pinfunction "VI_1") (pintype "input"))
      (node (ref "IC8") (pin "14") (pinfunction "VDD_14") (pintype "power_in"))
      (node (ref "IC9") (pin "14") (pinfunction "VDD_14") (pintype "power_in"))
      (node (ref "Q1") (pin "1") (pinfunction "D_1") (pintype "passive"))
      (node (ref "Q10") (pin "1") (pinfunction "C_1") (pintype "passive"))
      (node (ref "Q6") (pin "1") (pinfunction "C_1") (pintype "passive"))
      (node (ref "Q7") (pin "1") (pinfunction "C_1") (pintype "passive"))
      (node (ref "Q9") (pin "1") (pinfunction "C_1") (pintype "passive"))
      (node (ref "R10") (pin "2") (pinfunction "2_2") (pintype "passive"))
      (node (ref "R35") (pin "2") (pinfunction "2_2") (pintype "passive"))
      (node (ref "R40") (pin "2") (pinfunction "2_2") (pintype "passive"))
      (node (ref "R76") (pin "2") (pinfunction "2_2") (pintype "passive"))
      (node (ref "R79") (pin "2") (pinfunction "2_2") (pintype "passive"))
    )
    (net (code "2") (name "GND") (class "Default")
      (node (ref "C11") (pin "2") (pinfunction "2_2") (pintype "passive"))
      (node (ref "C12") (pin "2") (pinfunction "2_2") (pintype "passive"))
      (node (ref "C18") (pin "2") (pinfunction "2_2") (pintype "passive"))
      (node (ref "C19") (pin "-") (pinfunction "-_-") (pintype "passive"))
      (node (ref "C22") (pin "2") (pinfunction "2_2") (pintype "passive"))
      (node (ref "C23") (pin "-") (pinfunction "-_-") (pintype "passive"))
      (node (ref "C24") (pin "2") (pinfunction "2_2") (pintype "passive"))
      (node (ref "C25") (pin "2") (pinfunction "2_2") (pintype "passive"))
      (node (ref "C26") (pin "-") (pinfunction "-_-") (pintype "passive"))
      (node (ref "C27") (pin "-") (pinfunction "-_-") (pintype "passive"))
      (node (ref "C29") (pin "-") (pinfunction "-_-") (pintype "passive"))
      (node (ref "C30") (pin "2") (pinfunction "2_2") (pintype "passive"))
      (node (ref "C31") (pin "2") (pinfunction "2_2") (pintype "passive"))
      (node (ref "C32") (pin "2") (pinfunction "2_2") (pintype "passive"))
      (node (ref "C33") (pin "2") (pinfunction "2_2") (pintype "passive"))
      (node (ref "C34") (pin "2") (pinfunction "2_2") (pintype "passive"))
      (node (ref "C35") (pin "1") (pinfunction "1_1") (pintype "passive"))
      (node (ref "C37") (pin "2") (pinfunction "2_2") (pintype "passive"))
      (node (ref "C40") (pin "2") (pinfunction "2_2") (pintype "passive"))
      (node (ref "C42") (pin "-") (pinfunction "-_-") (pintype "passive"))
      (node (ref "C43") (pin "-") (pinfunction "-_-") (pintype "passive"))
      (node (ref "C45") (pin "2") (pinfunction "2_2") (pintype "passive"))
      (node (ref "C46") (pin "2") (pinfunction "2_2") (pintype "passive"))
      (node (ref "C5") (pin "-") (pinfunction "-_-") (pintype "passive"))
      (node (ref "C50") (pin "2") (pinfunction "2_2") (pintype "passive"))
      (node (ref "C51") (pin "2") (pinfunction "2_2") (pintype "passive"))
      (node (ref "C52") (pin "-") (pinfunction "-_-") (pintype "passive"))
      (node (ref "C54") (pin "-") (pinfunction "-_-") (pintype "passive"))
      (node (ref "C55") (pin "-") (pinfunction "-_-") (pintype "passive"))
      (node (ref "C56") (pin "-") (pinfunction "-_-") (pintype "passive"))
      (node (ref "C58") (pin "2") (pinfunction "2_2") (pintype "passive"))
      (node (ref "C6") (pin "-") (pinfunction "-_-") (pintype "passive"))
      (node (ref "D10_") (pin "A") (pinfunction "A_A") (pintype "passive"))
      (node (ref "D2") (pin "A") (pinfunction "A_A") (pintype "passive"))
      (node (ref "D3") (pin "C") (pinfunction "C_C") (pintype "passive"))
      (node (ref "FOOTSW") (pin "1") (pinfunction "P_1") (pintype "passive"))
      (node (ref "IC1") (pin "4") (pinfunction "V-_4") (pintype "power_in"))
      (node (ref "IC2") (pin "4") (pinfunction "V-_4") (pintype "power_in"))
      (node (ref "IC3") (pin "4") (pinfunction "V-_4") (pintype "power_in"))
      (node (ref "IC4") (pin "4") (pinfunction "V-_4") (pintype "power_in"))
      (node (ref "IC5") (pin "10") (pinfunction "R_10") (pintype "input"))
      (node (ref "IC5") (pin "3") (pinfunction "CLK_3") (pintype "input"))
      (node (ref "IC5") (pin "5") (pinfunction "D_5") (pintype "input"))
      (node (ref "IC5") (pin "7") (pinfunction "VSS_7") (pintype "power_in"))
      (node (ref "IC5") (pin "8") (pinfunction "S_8") (pintype "input"))
      (node (ref "IC6") (pin "2") (pinfunction "GND_2") (pintype "passive"))
      (node (ref "IC7") (pin "5") (pinfunction "INH_5") (pintype "input"))
      (node (ref "IC7") (pin "8") (pinfunction "VSS_8") (pintype "power_in"))
      (node (ref "IC8") (pin "3") (pinfunction "B_3") (pintype "tri_state"))
      (node (ref "IC8") (pin "4") (pinfunction "A_4") (pintype "tri_state"))
      (node (ref "IC8") (pin "5") (pinfunction "C_5") (pintype "input"))
      (node (ref "IC8") (pin "7") (pinfunction "VSS_7") (pintype "power_in"))
      (node (ref "IC9") (pin "7") (pinfunction "VSS_7") (pintype "power_in"))
      (node (ref "LEVEL") (pin "1") (pinfunction "1_1") (pintype "passive"))
      (node (ref "OVERTONE") (pin "2") (pinfunction "2_2") (pintype "passive"))
      (node (ref "Q11") (pin "3") (pinfunction "E_3") (pintype "passive"))
      (node (ref "Q12") (pin "3") (pinfunction "E_3") (pintype "passive"))
      (node (ref "Q13") (pin "3") (pinfunction "E_3") (pintype "passive"))
      (node (ref "Q14") (pin "3") (pinfunction "E_3") (pintype "passive"))
      (node (ref "Q15") (pin "3") (pinfunction "E_3") (pintype "passive"))
      (node (ref "R1") (pin "1") (pinfunction "1_1") (pintype "passive"))
      (node (ref "R14") (pin "1") (pinfunction "1_1") (pintype "passive"))
      (node (ref "R24") (pin "1") (pinfunction "1_1") (pintype "passive"))
      (node (ref "R26") (pin "1") (pinfunction "1_1") (pintype "passive"))
      (node (ref "R28") (pin "1") (pinfunction "1_1") (pintype "passive"))
      (node (ref "R29") (pin "1") (pinfunction "1_1") (pintype "passive"))
      (node (ref "R34") (pin "1") (pinfunction "1_1") (pintype "passive"))
      (node (ref "R37") (pin "1") (pinfunction "1_1") (pintype "passive"))
      (node (ref "R39_") (pin "1") (pinfunction "1_1") (pintype "passive"))
      (node (ref "R51") (pin "2") (pinfunction "2_2") (pintype "passive"))
      (node (ref "R52") (pin "2") (pinfunction "2_2") (pintype "passive"))
      (node (ref "R57") (pin "1") (pinfunction "1_1") (pintype "passive"))
      (node (ref "R6") (pin "1") (pinfunction "1_1") (pintype "passive"))
      (node (ref "R61") (pin "1") (pinfunction "1_1") (pintype "passive"))
      (node (ref "R66") (pin "1") (pinfunction "1_1") (pintype "passive"))
      (node (ref "R8") (pin "1") (pinfunction "1_1") (pintype "passive"))
      (node (ref "R81") (pin "1") (pinfunction "1_1") (pintype "passive"))
      (node (ref "R82") (pin "1") (pinfunction "1_1") (pintype "passive"))
      (node (ref "R85") (pin "1") (pinfunction "1_1") (pintype "passive"))
      (node (ref "R87") (pin "1") (pinfunction "1_1") (pintype "passive"))
      (node (ref "R9") (pin "1") (pinfunction "1_1") (pintype "passive"))
      (node (ref "R93") (pin "1") (pinfunction "1_1") (pintype "passive"))
      (node (ref "R95") (pin "1") (pinfunction "1_1") (pintype "passive"))
      (node (ref "R96") (pin "1") (pinfunction "1_1") (pintype "passive"))
    )
    (net (code "3") (name "IN") (class "Default")
      (node (ref "R2") (pin "1") (pinfunction "1_1") (pintype "passive"))
    )
    (net (code "4") (name "Net-(C1-Pad2)") (class "Default")
      (node (ref "C1") (pin "2") (pinfunction "2_2") (pintype "passive"))
      (node (ref "R2") (pin "2") (pinfunction "2_2") (pintype "passive"))
    )
    (net (code "5") (name "Net-(C3-Pad2)") (class "Default")
      (node (ref "C3") (pin "2") (pinfunction "2_2") (pintype "passive"))
      (node (ref "R3") (pin "2") (pinfunction "2_2") (pintype "passive"))
      (node (ref "R4") (pin "1") (pinfunction "1_1") (pintype "passive"))
    )
    (net (code "6") (name "Net-(C5-Pad+)") (class "Default")
      (node (ref "C5") (pin "+") (pinfunction "+_+") (pintype "passive"))
      (node (ref "R13") (pin "1") (pinfunction "1_1") (pintype "passive"))
    )
    (net (code "7") (name "Net-(C6-Pad+)") (class "Default")
      (node (ref "C6") (pin "+") (pinfunction "+_+") (pintype "passive"))
      (node (ref "R17") (pin "2") (pinfunction "2_2") (pintype "passive"))
    )
    (net (code "8") (name "Net-(C7-Pad1)") (class "Default")
      (node (ref "C7") (pin "1") (pinfunction "1_1") (pintype "passive"))
      (node (ref "R16") (pin "1") (pinfunction "1_1") (pintype "passive"))
    )
    (net (code "9") (name "Net-(C8-Pad-)") (class "Default")
      (node (ref "C8") (pin "-") (pinfunction "-_-") (pintype "passive"))
      (node (ref "TONE") (pin "2") (pinfunction "2_2") (pintype "passive"))
    )
    (net (code "10") (name "Net-(C9-Pad-)") (class "Default")
      (node (ref "C9") (pin "-") (pinfunction "-_-") (pintype "passive"))
      (node (ref "R19") (pin "1") (pinfunction "1_1") (pintype "passive"))
    )
    (net (code "11") (name "Net-(C10-Pad-)") (class "Default")
      (node (ref "C10") (pin "-") (pinfunction "-_-") (pintype "passive"))
      (node (ref "R22") (pin "1") (pinfunction "1_1") (pintype "passive"))
    )
    (net (code "12") (name "Net-(C11-Pad1)") (class "Default")
      (node (ref "C11") (pin "1") (pinfunction "1_1") (pintype "passive"))
      (node (ref "C13") (pin "2") (pinfunction "2_2") (pintype "passive"))
      (node (ref "D2") (pin "C") (pinfunction "C_C") (pintype "passive"))
      (node (ref "D3") (pin "A") (pinfunction "A_A") (pintype "passive"))
      (node (ref "R21") (pin "1") (pinfunction "1_1") (pintype "passive"))
      (node (ref "R22") (pin "2") (pinfunction "2_2") (pintype "passive"))
    )
    (net (code "13") (name "Net-(C12-Pad1)") (class "Default")
      (node (ref "C12") (pin "1") (pinfunction "1_1") (pintype "passive"))
      (node (ref "R21") (pin "2") (pinfunction "2_2") (pintype "passive"))
      (node (ref "TONE") (pin "1") (pinfunction "1_1") (pintype "passive"))
    )
    (net (code "14") (name "Net-(C13-Pad1)") (class "Default")
      (node (ref "C13") (pin "1") (pinfunction "1_1") (pintype "passive"))
      (node (ref "R23") (pin "1") (pinfunction "1_1") (pintype "passive"))
    )
    (net (code "15") (name "Net-(C14-Pad-)") (class "Default")
      (node (ref "C14") (pin "-") (pinfunction "-_-") (pintype "passive"))
      (node (ref "LEVEL") (pin "2") (pinfunction "2_2") (pintype "passive"))
    )
    (net (code "16") (name "Net-(C15-Pad-)") (class "Default")
      (node (ref "C15") (pin "-") (pinfunction "-_-") (pintype "passive"))
      (node (ref "R27") (pin "1") (pinfunction "1_1") (pintype "passive"))
      (node (ref "R28") (pin "2") (pinfunction "2_2") (pintype "passive"))
    )
    (net (code "17") (name "Net-(C17-Pad1)") (class "Default")
      (node (ref "C17") (pin "1") (pinfunction "1_1") (pintype "passive"))
      (node (ref "DIST") (pin "2") (pinfunction "2_2") (pintype "passive"))
      (node (ref "DIST") (pin "3") (pinfunction "3_3") (pintype "passive"))
      (node (ref "R18") (pin "2") (pinfunction "2_2") (pintype "passive"))
    )
    (net (code "18") (name "Net-(C18-Pad1)") (class "Default")
      (node (ref "C18") (pin "1") (pinfunction "1_1") (pintype "passive"))
      (node (ref "R12") (pin "2") (pinfunction "2_2") (pintype "passive"))
      (node (ref "R36") (pin "1") (pinfunction "1_1") (pintype "passive"))
    )
    (net (code "19") (name "Net-(C20-Pad2)") (class "Default")
      (node (ref "C20") (pin "2") (pinfunction "2_2") (pintype "passive"))
      (node (ref "R36") (pin "2") (pinfunction "2_2") (pintype "passive"))
      (node (ref "R39") (pin "1") (pinfunction "1_1") (pintype "passive"))
    )
    (net (code "20") (name "Net-(C24-Pad1)") (class "Default")
      (node (ref "C24") (pin "1") (pinfunction "1_1") (pintype "passive"))
      (node (ref "D4") (pin "C") (pinfunction "C_C") (pintype "passive"))
      (node (ref "R48") (pin "2") (pinfunction "2_2") (pintype "passive"))
    )
    (net (code "21") (name "Net-(C25-Pad1)") (class "Default")
      (node (ref "C25") (pin "1") (pinfunction "1_1") (pintype "passive"))
      (node (ref "D5") (pin "C") (pinfunction "C_C") (pintype "passive"))
      (node (ref "D6") (pin "C") (pinfunction "C_C") (pintype "passive"))
      (node (ref "R49") (pin "2") (pinfunction "2_2") (pintype "passive"))
    )
    (net (code "22") (name "Net-(C28-Pad2)") (class "Default")
      (node (ref "C28") (pin "2") (pinfunction "2_2") (pintype "passive"))
      (node (ref "R57") (pin "2") (pinfunction "2_2") (pintype "passive"))
    )
    (net (code "23") (name "Net-(C35-Pad2)") (class "Default")
      (node (ref "C35") (pin "2") (pinfunction "2_2") (pintype "passive"))
      (node (ref "R44") (pin "2") (pinfunction "2_2") (pintype "passive"))
      (node (ref "R62") (pin "2") (pinfunction "2_2") (pintype "passive"))
    )
    (net (code "24") (name "Net-(C36-Pad1)") (class "Default")
      (node (ref "C36") (pin "1") (pinfunction "1_1") (pintype "passive"))
      (node (ref "R62") (pin "1") (pinfunction "1_1") (pintype "passive"))
    )
    (net (code "25") (name "Net-(C36-Pad2)") (class "Default")
      (node (ref "C36") (pin "2") (pinfunction "2_2") (pintype "passive"))
      (node (ref "C37") (pin "1") (pinfunction "1_1") (pintype "passive"))
      (node (ref "R60") (pin "2") (pinfunction "2_2") (pintype "passive"))
    )
    (net (code "26") (name "Net-(C38-Pad-)") (class "Default")
      (node (ref "C38") (pin "-") (pinfunction "-_-") (pintype "passive"))
      (node (ref "R64") (pin "2") (pinfunction "2_2") (pintype "passive"))
      (node (ref "R65") (pin "2") (pinfunction "2_2") (pintype "passive"))
    )
    (net (code "27") (name "Net-(C39-Pad1)") (class "Default")
      (node (ref "C39") (pin "1") (pinfunction "1_1") (pintype "passive"))
      (node (ref "IC7") (pin "6") (pinfunction "CX_6") (pintype "input"))
    )
    (net (code "28") (name "Net-(C39-Pad2)") (class "Default")
      (node (ref "C39") (pin "2") (pinfunction "2_2") (pintype "passive"))
      (node (ref "IC7") (pin "7") (pinfunction "CX_7") (pintype "input"))
    )
    (net (code "29") (name "Net-(C40-Pad1)") (class "Default")
      (node (ref "C40") (pin "1") (pinfunction "1_1") (pintype "passive"))
      (node (ref "C47") (pin "-") (pinfunction "-_-") (pintype "passive"))
      (node (ref "R67") (pin "2") (pinfunction "2_2") (pintype "passive"))
      (node (ref "R68") (pin "1") (pinfunction "1_1") (pintype "passive"))
    )
    (net (code "30") (name "Net-(C41-Pad+)") (class "Default")
      (node (ref "C41") (pin "+") (pinfunction "+_+") (pintype "passive"))
      (node (ref "C46") (pin "1") (pinfunction "1_1") (pintype "passive"))
      (node (ref "R70") (pin "1") (pinfunction "1_1") (pintype "passive"))
    )
    (net (code "31") (name "Net-(C41-Pad-)") (class "Default")
      (node (ref "C41") (pin "-") (pinfunction "-_-") (pintype "passive"))
      (node (ref "OVERTONE") (pin "3") (pinfunction "3_3") (pintype "passive"))
      (node (ref "R68") (pin "2") (pinfunction "2_2") (pintype "passive"))
    )
    (net (code "32") (name "Net-(C44-Pad+)") (class "Default")
      (node (ref "C44") (pin "+") (pinfunction "+_+") (pintype "passive"))
      (node (ref "C45") (pin "1") (pinfunction "1_1") (pintype "passive"))
      (node (ref "R74") (pin "1") (pinfunction "1_1") (pintype "passive"))
    )
    (net (code "33") (name "Net-(C44-Pad-)") (class "Default")
      (node (ref "C44") (pin "-") (pinfunction "-_-") (pintype "passive"))
      (node (ref "OVERTONE") (pin "1") (pinfunction "1_1") (pintype "passive"))
      (node (ref "R67") (pin "1") (pinfunction "1_1") (pintype "passive"))
    )
    (net (code "34") (name "Net-(C48-Pad1)") (class "Default")
      (node (ref "C48") (pin "1") (pinfunction "1_1") (pintype "passive"))
      (node (ref "R63") (pin "2") (pinfunction "2_2") (pintype "passive"))
      (node (ref "R64") (pin "1") (pinfunction "1_1") (pintype "passive"))
    )
    (net (code "35") (name "Net-(C49-Pad2)") (class "Default")
      (node (ref "C49") (pin "2") (pinfunction "2_2") (pintype "passive"))
      (node (ref "R4") (pin "2") (pinfunction "2_2") (pintype "passive"))
    )
    (net (code "36") (name "Net-(C51-Pad1)") (class "Default")
      (node (ref "C51") (pin "1") (pinfunction "1_1") (pintype "passive"))
      (node (ref "D12") (pin "C") (pinfunction "C_C") (pintype "passive"))
      (node (ref "R92") (pin "2") (pinfunction "2_2") (pintype "passive"))
    )
    (net (code "37") (name "Net-(C53-Pad-)") (class "Default")
      (node (ref "C53") (pin "-") (pinfunction "-_-") (pintype "passive"))
      (node (ref "D13") (pin "A") (pinfunction "A_A") (pintype "passive"))
      (node (ref "R96") (pin "2") (pinfunction "2_2") (pintype "passive"))
    )
    (net (code "38") (name "Net-(CHECK-A)") (class "Default")
      (node (ref "CHECK") (pin "ANODE") (pinfunction "A_ANODE") (pintype "passive"))
      (node (ref "D20") (pin "A") (pinfunction "A_A") (pintype "passive"))
    )
    (net (code "39") (name "Net-(CHECK-C)") (class "Default")
      (node (ref "CHECK") (pin "P$1") (pinfunction "C_P$1") (pintype "passive"))
      (node (ref "Q15") (pin "1") (pinfunction "C_1") (pintype "passive"))
    )
    (net (code "40") (name "Net-(D9-PadC)") (class "Default")
      (node (ref "D9") (pin "C") (pinfunction "C_C") (pintype "passive"))
      (node (ref "R47") (pin "1") (pinfunction "1_1") (pintype "passive"))
      (node (ref "R55") (pin "2") (pinfunction "2_2") (pintype "passive"))
    )
    (net (code "41") (name "Net-(D11-PadA)") (class "Default")
      (node (ref "D11") (pin "A") (pinfunction "A_A") (pintype "passive"))
      (node (ref "R54") (pin "1") (pinfunction "1_1") (pintype "passive"))
      (node (ref "R56") (pin "2") (pinfunction "2_2") (pintype "passive"))
    )
    (net (code "42") (name "Net-(D13-PadC)") (class "Default")
      (node (ref "D13") (pin "C") (pinfunction "C_C") (pintype "passive"))
      (node (ref "R91") (pin "2") (pinfunction "2_2") (pintype "passive"))
    )
    (net (code "43") (name "Net-(D14-PadC)") (class "Default")
      (node (ref "D14") (pin "C") (pinfunction "C_C") (pintype "passive"))
      (node (ref "R90") (pin "2") (pinfunction "2_2") (pintype "passive"))
    )
    (net (code "44") (name "Net-(D15-PadC)") (class "Default")
      (node (ref "D15") (pin "C") (pinfunction "C_C") (pintype "passive"))
      (node (ref "R83") (pin "2") (pinfunction "2_2") (pintype "passive"))
    )
    (net (code "45") (name "Net-(D16-PadA)") (class "Default")
      (node (ref "D16") (pin "A") (pinfunction "A_A") (pintype "passive"))
      (node (ref "R86") (pin "1") (pinfunction "1_1") (pintype "passive"))
      (node (ref "R87") (pin "2") (pinfunction "2_2") (pintype "passive"))
    )
    (net (code "46") (name "Net-(D18-PadA)") (class "Default")
      (node (ref "D18") (pin "A") (pinfunction "A_A") (pintype "passive"))
      (node (ref "R80") (pin "2") (pinfunction "2_2") (pintype "passive"))
    )
    (net (code "47") (name "Net-(FOOTSW-S)") (class "Default")
      (node (ref "FOOTSW") (pin "2") (pinfunction "S_2") (pintype "passive"))
      (node (ref "R77") (pin "1") (pinfunction "1_1") (pintype "passive"))
    )
    (net (code "48") (name "Net-(IC1A-+IN)") (class "Default")
      (node (ref "IC1") (pin "3") (pinfunction "+IN_3") (pintype "input"))
      (node (ref "R15") (pin "2") (pinfunction "2_2") (pintype "passive"))
      (node (ref "R16") (pin "2") (pinfunction "2_2") (pintype "passive"))
    )
    (net (code "49") (name "Net-(IC1A--IN)") (class "Default")
      (node (ref "IC1") (pin "2") (pinfunction "-IN_2") (pintype "input"))
      (node (ref "R17") (pin "1") (pinfunction "1_1") (pintype "passive"))
      (node (ref "R18") (pin "1") (pinfunction "1_1") (pintype "passive"))
    )
    (net (code "50") (name "Net-(IC1A-OUT)") (class "Default")
      (node (ref "C10") (pin "+") (pinfunction "+_+") (pintype "passive"))
      (node (ref "DIST") (pin "1") (pinfunction "1_1") (pintype "passive"))
      (node (ref "IC1") (pin "1") (pinfunction "OUT_1") (pintype "output"))
      (node (ref "Q3") (pin "1") (pinfunction "D_1") (pintype "passive"))
    )
    (net (code "51") (name "Net-(IC1B-+IN)") (class "Default")
      (node (ref "C4") (pin "-") (pinfunction "-_-") (pintype "passive"))
      (node (ref "IC1") (pin "5") (pinfunction "+IN_5") (pintype "input"))
      (node (ref "R9") (pin "2") (pinfunction "2_2") (pintype "passive"))
    )
    (net (code "52") (name "Net-(IC1B--IN)") (class "Default")
      (node (ref "IC1") (pin "6") (pinfunction "-IN_6") (pintype "input"))
      (node (ref "R11") (pin "1") (pinfunction "1_1") (pintype "passive"))
      (node (ref "R13") (pin "2") (pinfunction "2_2") (pintype "passive"))
    )
    (net (code "53") (name "Net-(IC1B-OUT)") (class "Default")
      (node (ref "IC1") (pin "7") (pinfunction "OUT_7") (pintype "output"))
      (node (ref "R11") (pin "2") (pinfunction "2_2") (pintype "passive"))
      (node (ref "R12") (pin "1") (pinfunction "1_1") (pintype "passive"))
    )
    (net (code "54") (name "Net-(IC2A-+IN)") (class "Default")
      (node (ref "IC2") (pin "3") (pinfunction "+IN_3") (pintype "input"))
      (node (ref "R39_") (pin "2") (pinfunction "2_2") (pintype "passive"))
      (node (ref "R40") (pin "1") (pinfunction "1_1") (pintype "passive"))
      (node (ref "R41") (pin "1") (pinfunction "1_1") (pintype "passive"))
    )
    (net (code "55") (name "Net-(IC2A--IN)") (class "Default")
      (node (ref "C31") (pin "1") (pinfunction "1_1") (pintype "passive"))
      (node (ref "C32") (pin "1") (pinfunction "1_1") (pintype "passive"))
      (node (ref "IC2") (pin "2") (pinfunction "-IN_2") (pintype "input"))
      (node (ref "R42") (pin "1") (pinfunction "1_1") (pintype "passive"))
      (node (ref "R44") (pin "1") (pinfunction "1_1") (pintype "passive"))
    )
    (net (code "56") (name "Net-(IC2A-OUT)") (class "Default")
      (node (ref "C34") (pin "1") (pinfunction "1_1") (pintype "passive"))
      (node (ref "IC2") (pin "1") (pinfunction "OUT_1") (pintype "output"))
      (node (ref "R41") (pin "2") (pinfunction "2_2") (pintype "passive"))
      (node (ref "R42") (pin "2") (pinfunction "2_2") (pintype "passive"))
      (node (ref "R43") (pin "2") (pinfunction "2_2") (pintype "passive"))
    )
    (net (code "57") (name "Net-(IC2B-+IN)") (class "Default")
      (node (ref "C33") (pin "1") (pinfunction "1_1") (pintype "passive"))
      (node (ref "IC2") (pin "5") (pinfunction "+IN_5") (pintype "input"))
      (node (ref "R39") (pin "2") (pinfunction "2_2") (pintype "passive"))
    )
    (net (code "58") (name "Net-(IC2B--IN)") (class "Default")
      (node (ref "C20") (pin "1") (pinfunction "1_1") (pintype "passive"))
      (node (ref "IC2") (pin "6") (pinfunction "-IN_6") (pintype "input"))
      (node (ref "IC2") (pin "7") (pinfunction "OUT_7") (pintype "output"))
      (node (ref "R38") (pin "1") (pinfunction "1_1") (pintype "passive"))
    )
    (net (code "59") (name "Net-(IC3A-+IN)") (class "Default")
      (node (ref "C28") (pin "1") (pinfunction "1_1") (pintype "passive"))
      (node (ref "IC3") (pin "3") (pinfunction "+IN_3") (pintype "input"))
      (node (ref "IC3") (pin "5") (pinfunction "+IN_5") (pintype "input"))
      (node (ref "R46") (pin "2") (pinfunction "2_2") (pintype "passive"))
    )
    (net (code "60") (name "Net-(IC3A--IN)") (class "Default")
      (node (ref "D10") (pin "C") (pinfunction "C_C") (pintype "passive"))
      (node (ref "IC3") (pin "2") (pinfunction "-IN_2") (pintype "input"))
      (node (ref "R56") (pin "1") (pinfunction "1_1") (pintype "passive"))
    )
    (net (code "61") (name "Net-(IC3A-OUT)") (class "Default")
      (node (ref "D10") (pin "A") (pinfunction "A_A") (pintype "passive"))
      (node (ref "D11") (pin "C") (pinfunction "C_C") (pintype "passive"))
      (node (ref "IC3") (pin "1") (pinfunction "OUT_1") (pintype "output"))
    )
    (net (code "62") (name "Net-(IC3B--IN)") (class "Default")
      (node (ref "D7") (pin "A") (pinfunction "A_A") (pintype "passive"))
      (node (ref "IC3") (pin "6") (pinfunction "-IN_6") (pintype "input"))
      (node (ref "R55") (pin "1") (pinfunction "1_1") (pintype "passive"))
    )
    (net (code "63") (name "Net-(IC3B-OUT)") (class "Default")
      (node (ref "D7") (pin "C") (pinfunction "C_C") (pintype "passive"))
      (node (ref "D9") (pin "A") (pinfunction "A_A") (pintype "passive"))
      (node (ref "IC3") (pin "7") (pinfunction "OUT_7") (pintype "output"))
    )
    (net (code "64") (name "Net-(IC4A-+IN)") (class "Default")
      (node (ref "C26") (pin "+") (pinfunction "+_+") (pintype "passive"))
      (node (ref "IC4") (pin "3") (pinfunction "+IN_3") (pintype "input"))
      (node (ref "R54") (pin "2") (pinfunction "2_2") (pintype "passive"))
    )
    (net (code "65") (name "Net-(IC4A--IN)") (class "Default")
      (node (ref "C22") (pin "1") (pinfunction "1_1") (pintype "passive"))
      (node (ref "IC4") (pin "2") (pinfunction "-IN_2") (pintype "input"))
      (node (ref "IC4") (pin "5") (pinfunction "+IN_5") (pintype "input"))
      (node (ref "R38") (pin "2") (pinfunction "2_2") (pintype "passive"))
      (node (ref "R46") (pin "1") (pinfunction "1_1") (pintype "passive"))
    )
    (net (code "66") (name "Net-(IC4A-OUT)") (class "Default")
      (node (ref "IC4") (pin "1") (pinfunction "OUT_1") (pintype "output"))
      (node (ref "R53") (pin "1") (pinfunction "1_1") (pintype "passive"))
    )
    (net (code "67") (name "Net-(IC4B--IN)") (class "Default")
      (node (ref "C27") (pin "+") (pinfunction "+_+") (pintype "passive"))
      (node (ref "IC4") (pin "6") (pinfunction "-IN_6") (pintype "input"))
      (node (ref "R47") (pin "2") (pinfunction "2_2") (pintype "passive"))
    )
    (net (code "68") (name "Net-(IC4B-OUT)") (class "Default")
      (node (ref "IC4") (pin "7") (pinfunction "OUT_7") (pintype "output"))
      (node (ref "R50") (pin "1") (pinfunction "1_1") (pintype "passive"))
    )
    (net (code "69") (name "Net-(IC5A-Q)") (class "Default")
      (node (ref "IC5") (pin "1") (pinfunction "Q_1") (pintype "output"))
      (node (ref "IC5") (pin "2") (pinfunction "~{Q}_2") (pintype "output"))
      (node (ref "R58") (pin "2") (pinfunction "2_2") (pintype "passive"))
    )
    (net (code "70") (name "Net-(IC5A-R)") (class "Default")
      (node (ref "IC5") (pin "4") (pinfunction "R_4") (pintype "input"))
      (node (ref "R52") (pin "1") (pinfunction "1_1") (pintype "passive"))
      (node (ref "R53") (pin "2") (pinfunction "2_2") (pintype "passive"))
    )
    (net (code "71") (name "Net-(IC5A-S)") (class "Default")
      (node (ref "IC5") (pin "6") (pinfunction "S_6") (pintype "input"))
      (node (ref "R50") (pin "2") (pinfunction "2_2") (pintype "passive"))
      (node (ref "R51") (pin "1") (pinfunction "1_1") (pintype "passive"))
    )
    (net (code "72") (name "Net-(IC5B-CLK)") (class "Default")
      (node (ref "IC5") (pin "11") (pinfunction "CLK_11") (pintype "input"))
      (node (ref "IC7") (pin "4") (pinfunction "VCOOUT_4") (pintype "output"))
      (node (ref "R71") (pin "2") (pinfunction "2_2") (pintype "passive"))
    )
    (net (code "73") (name "Net-(IC5B-D)") (class "Default")
      (node (ref "IC5") (pin "12") (pinfunction "~{Q}_12") (pintype "output"))
      (node (ref "IC5") (pin "9") (pinfunction "D_9") (pintype "input"))
    )
    (net (code "74") (name "Net-(IC5B-Q)") (class "Default")
      (node (ref "IC5") (pin "13") (pinfunction "Q_13") (pintype "output"))
      (node (ref "IC7") (pin "3") (pinfunction "CIN_3") (pintype "input"))
      (node (ref "R69") (pin "2") (pinfunction "2_2") (pintype "passive"))
    )
    (net (code "75") (name "Net-(IC7A-PC2)") (class "Default")
      (node (ref "IC7") (pin "13") (pinfunction "PC2_13") (pintype "output"))
      (node (ref "R59") (pin "1") (pinfunction "1_1") (pintype "passive"))
    )
    (net (code "76") (name "Net-(IC7A-R1)") (class "Default")
      (node (ref "IC7") (pin "11") (pinfunction "R1_11") (pintype "input"))
      (node (ref "R61") (pin "2") (pinfunction "2_2") (pintype "passive"))
    )
    (net (code "77") (name "Net-(IC7A-SIGIN)") (class "Default")
      (node (ref "IC7") (pin "14") (pinfunction "SIGIN_14") (pintype "input"))
      (node (ref "R58") (pin "1") (pinfunction "1_1") (pintype "passive"))
    )
    (net (code "78") (name "Net-(IC7A-VCOIN)") (class "Default")
      (node (ref "IC7") (pin "9") (pinfunction "VCOIN_9") (pintype "input"))
      (node (ref "IC8") (pin "2") (pinfunction "B_2") (pintype "tri_state"))
      (node (ref "R60") (pin "1") (pinfunction "1_1") (pintype "passive"))
    )
    (net (code "79") (name "Net-(IC8A-A)") (class "Default")
      (node (ref "IC8") (pin "1") (pinfunction "A_1") (pintype "tri_state"))
      (node (ref "R59") (pin "2") (pinfunction "2_2") (pintype "passive"))
    )
    (net (code "80") (name "Net-(IC8A-C)") (class "Default")
      (node (ref "C29") (pin "+") (pinfunction "+_+") (pintype "passive"))
      (node (ref "D8") (pin "A") (pinfunction "A_A") (pintype "passive"))
      (node (ref "IC8") (pin "13") (pinfunction "C_13") (pintype "input"))
      (node (ref "R45") (pin "2") (pinfunction "2_2") (pintype "passive"))
    )
    (net (code "81") (name "Net-(IC8C-A)") (class "Default")
      (node (ref "IC8") (pin "8") (pinfunction "A_8") (pintype "tri_state"))
      (node (ref "R43") (pin "1") (pinfunction "1_1") (pintype "passive"))
    )
    (net (code "82") (name "Net-(IC8C-B)") (class "Default")
      (node (ref "IC8") (pin "10") (pinfunction "B_10") (pintype "tri_state"))
      (node (ref "IC8") (pin "9") (pinfunction "B_9") (pintype "tri_state"))
      (node (ref "R94") (pin "2") (pinfunction "2_2") (pintype "passive"))
    )
    (net (code "83") (name "Net-(IC8C-C)") (class "Default")
      (node (ref "C53") (pin "+") (pinfunction "+_+") (pintype "passive"))
      (node (ref "C57") (pin "2") (pinfunction "2_2") (pintype "passive"))
      (node (ref "IC8") (pin "6") (pinfunction "C_6") (pintype "input"))
      (node (ref "IC9") (pin "13") (pinfunction "I1_13") (pintype "input"))
      (node (ref "IC9") (pin "3") (pinfunction "O_3") (pintype "output"))
      (node (ref "R80") (pin "1") (pinfunction "1_1") (pintype "passive"))
      (node (ref "R88") (pin "2") (pinfunction "2_2") (pintype "passive"))
      (node (ref "R89") (pin "1") (pinfunction "1_1") (pintype "passive"))
      (node (ref "R90") (pin "1") (pinfunction "1_1") (pintype "passive"))
    )
    (net (code "84") (name "Net-(IC8D-A)") (class "Default")
      (node (ref "C30") (pin "1") (pinfunction "1_1") (pintype "passive"))
      (node (ref "IC8") (pin "11") (pinfunction "A_11") (pintype "tri_state"))
      (node (ref "R75") (pin "2") (pinfunction "2_2") (pintype "passive"))
    )
    (net (code "85") (name "Net-(IC8D-C)") (class "Default")
      (node (ref "D8") (pin "C") (pinfunction "C_C") (pintype "passive"))
      (node (ref "IC8") (pin "12") (pinfunction "C_12") (pintype "input"))
      (node (ref "Q14") (pin "1") (pinfunction "C_1") (pintype "passive"))
      (node (ref "R45") (pin "1") (pinfunction "1_1") (pintype "passive"))
      (node (ref "R78") (pin "1") (pinfunction "1_1") (pintype "passive"))
      (node (ref "R92") (pin "1") (pinfunction "1_1") (pintype "passive"))
    )
    (net (code "86") (name "Net-(IC9A-I0)") (class "Default")
      (node (ref "C58") (pin "1") (pinfunction "1_1") (pintype "passive"))
      (node (ref "IC9") (pin "1") (pinfunction "I0_1") (pintype "input"))
      (node (ref "IC9") (pin "2") (pinfunction "I1_2") (pintype "input"))
      (node (ref "R76") (pin "1") (pinfunction "1_1") (pintype "passive"))
      (node (ref "R77") (pin "2") (pinfunction "2_2") (pintype "passive"))
      (node (ref "R78") (pin "2") (pinfunction "2_2") (pintype "passive"))
    )
    (net (code "87") (name "Net-(IC9B-I0)") (class "Default")
      (node (ref "D17") (pin "C") (pinfunction "C_C") (pintype "passive"))
      (node (ref "D18") (pin "C") (pinfunction "C_C") (pintype "passive"))
      (node (ref "IC9") (pin "5") (pinfunction "I0_5") (pintype "input"))
      (node (ref "R81") (pin "2") (pinfunction "2_2") (pintype "passive"))
    )
    (net (code "88") (name "Net-(IC9B-I1)") (class "Default")
      (node (ref "C56") (pin "+") (pinfunction "+_+") (pintype "passive"))
      (node (ref "IC9") (pin "6") (pinfunction "I1_6") (pintype "input"))
      (node (ref "R83") (pin "1") (pinfunction "1_1") (pintype "passive"))
      (node (ref "R84") (pin "1") (pinfunction "1_1") (pintype "passive"))
    )
    (net (code "89") (name "Net-(IC9B-O)") (class "Default")
      (node (ref "IC9") (pin "4") (pinfunction "O_4") (pintype "output"))
      (node (ref "IC9") (pin "8") (pinfunction "I0_8") (pintype "input"))
    )
    (net (code "90") (name "Net-(IC9C-I1)") (class "Default")
      (node (ref "D15") (pin "A") (pinfunction "A_A") (pintype "passive"))
      (node (ref "IC9") (pin "11") (pinfunction "O_11") (pintype "output"))
      (node (ref "IC9") (pin "9") (pinfunction "I1_9") (pintype "input"))
      (node (ref "R49") (pin "1") (pinfunction "1_1") (pintype "passive"))
      (node (ref "R84") (pin "2") (pinfunction "2_2") (pintype "passive"))
      (node (ref "R86") (pin "2") (pinfunction "2_2") (pintype "passive"))
    )
    (net (code "91") (name "Net-(IC9C-O)") (class "Default")
      (node (ref "IC9") (pin "10") (pinfunction "O_10") (pintype "output"))
      (node (ref "IC9") (pin "12") (pinfunction "I0_12") (pintype "input"))
      (node (ref "R48") (pin "1") (pinfunction "1_1") (pintype "passive"))
      (node (ref "R75") (pin "1") (pinfunction "1_1") (pintype "passive"))
    )
    (net (code "92") (name "Net-(LEVEL-Pad3)") (class "Default")
      (node (ref "LEVEL") (pin "3") (pinfunction "3_3") (pintype "passive"))
      (node (ref "R19") (pin "2") (pinfunction "2_2") (pintype "passive"))
    )
    (net (code "93") (name "Net-(Q1-G)") (class "Default")
      (node (ref "C1") (pin "1") (pinfunction "1_1") (pintype "passive"))
      (node (ref "Q1") (pin "2") (pinfunction "G_2") (pintype "passive"))
      (node (ref "R8") (pin "2") (pinfunction "2_2") (pintype "passive"))
    )
    (net (code "94") (name "Net-(Q1-S)") (class "Default")
      (node (ref "C21") (pin "+") (pinfunction "+_+") (pintype "passive"))
      (node (ref "C4") (pin "+") (pinfunction "+_+") (pintype "passive"))
      (node (ref "Q1") (pin "3") (pinfunction "S_3") (pintype "passive"))
      (node (ref "R1") (pin "2") (pinfunction "2_2") (pintype "passive"))
      (node (ref "R3") (pin "1") (pinfunction "1_1") (pintype "passive"))
    )
    (net (code "95") (name "Net-(Q2-B)") (class "Default")
      (node (ref "C2") (pin "2") (pinfunction "2_2") (pintype "passive"))
      (node (ref "C3") (pin "1") (pinfunction "1_1") (pintype "passive"))
      (node (ref "Q2") (pin "2") (pinfunction "B_2") (pintype "passive"))
      (node (ref "R6") (pin "2") (pinfunction "2_2") (pintype "passive"))
      (node (ref "R7") (pin "1") (pinfunction "1_1") (pintype "passive"))
    )
    (net (code "96") (name "Net-(Q2-C)") (class "Default")
      (node (ref "C2") (pin "1") (pinfunction "1_1") (pintype "passive"))
      (node (ref "C7") (pin "2") (pinfunction "2_2") (pintype "passive"))
      (node (ref "Q2") (pin "1") (pinfunction "C_1") (pintype "passive"))
      (node (ref "R10") (pin "1") (pinfunction "1_1") (pintype "passive"))
      (node (ref "R7") (pin "2") (pinfunction "2_2") (pintype "passive"))
    )
    (net (code "97") (name "Net-(Q2-E)") (class "Default")
      (node (ref "Q2") (pin "3") (pinfunction "E_3") (pintype "passive"))
      (node (ref "R14") (pin "2") (pinfunction "2_2") (pintype "passive"))
    )
    (net (code "98") (name "Net-(Q3-G)") (class "Default")
      (node (ref "D5") (pin "A") (pinfunction "A_A") (pintype "passive"))
      (node (ref "Q3") (pin "2") (pinfunction "G_2") (pintype "passive"))
    )
    (net (code "99") (name "Net-(Q3-S)") (class "Default")
      (node (ref "C17") (pin "2") (pinfunction "2_2") (pintype "passive"))
      (node (ref "Q3") (pin "3") (pinfunction "S_3") (pintype "passive"))
    )
    (net (code "100") (name "Net-(Q4-D)") (class "Default")
      (node (ref "C21") (pin "-") (pinfunction "-_-") (pintype "passive"))
      (node (ref "Q4") (pin "1") (pinfunction "D_1") (pintype "passive"))
      (node (ref "R33") (pin "1") (pinfunction "1_1") (pintype "passive"))
    )
    (net (code "101") (name "Net-(Q4-G)") (class "Default")
      (node (ref "D6") (pin "A") (pinfunction "A_A") (pintype "passive"))
      (node (ref "Q4") (pin "2") (pinfunction "G_2") (pintype "passive"))
    )
    (net (code "102") (name "Net-(Q4-S)") (class "Default")
      (node (ref "C16") (pin "1") (pinfunction "1_1") (pintype "passive"))
      (node (ref "Q4") (pin "3") (pinfunction "S_3") (pintype "passive"))
      (node (ref "Q5") (pin "1") (pinfunction "D_1") (pintype "passive"))
      (node (ref "R37") (pin "2") (pinfunction "2_2") (pintype "passive"))
    )
    (net (code "103") (name "Net-(Q5-G)") (class "Default")
      (node (ref "D4") (pin "A") (pinfunction "A_A") (pintype "passive"))
      (node (ref "Q5") (pin "2") (pinfunction "G_2") (pintype "passive"))
    )
    (net (code "104") (name "Net-(Q5-S)") (class "Default")
      (node (ref "C14") (pin "+") (pinfunction "+_+") (pintype "passive"))
      (node (ref "Q5") (pin "3") (pinfunction "S_3") (pintype "passive"))
      (node (ref "R32") (pin "2") (pinfunction "2_2") (pintype "passive"))
    )
    (net (code "105") (name "Net-(Q6-B)") (class "Default")
      (node (ref "C8") (pin "+") (pinfunction "+_+") (pintype "passive"))
      (node (ref "Q6") (pin "2") (pinfunction "B_2") (pintype "passive"))
      (node (ref "R20") (pin "2") (pinfunction "2_2") (pintype "passive"))
    )
    (net (code "106") (name "Net-(Q6-E)") (class "Default")
      (node (ref "C9") (pin "+") (pinfunction "+_+") (pintype "passive"))
      (node (ref "Q6") (pin "3") (pinfunction "E_3") (pintype "passive"))
      (node (ref "R26") (pin "2") (pinfunction "2_2") (pintype "passive"))
    )
    (net (code "107") (name "Net-(Q7-B)") (class "Default")
      (node (ref "C16") (pin "2") (pinfunction "2_2") (pintype "passive"))
      (node (ref "Q7") (pin "2") (pinfunction "B_2") (pintype "passive"))
      (node (ref "R30") (pin "2") (pinfunction "2_2") (pintype "passive"))
    )
    (net (code "108") (name "Net-(Q7-E)") (class "Default")
      (node (ref "C15") (pin "+") (pinfunction "+_+") (pintype "passive"))
      (node (ref "Q7") (pin "3") (pinfunction "E_3") (pintype "passive"))
      (node (ref "R29") (pin "2") (pinfunction "2_2") (pintype "passive"))
    )
    (net (code "109") (name "Net-(Q8-G)") (class "Default")
      (node (ref "D12") (pin "A") (pinfunction "A_A") (pintype "passive"))
      (node (ref "Q8") (pin "2") (pinfunction "G_2") (pintype "passive"))
    )
    (net (code "110") (name "Net-(Q8-S)") (class "Default")
      (node (ref "C38") (pin "+") (pinfunction "+_+") (pintype "passive"))
      (node (ref "C47") (pin "+") (pinfunction "+_+") (pintype "passive"))
      (node (ref "Q8") (pin "3") (pinfunction "S_3") (pintype "passive"))
      (node (ref "R66") (pin "2") (pinfunction "2_2") (pintype "passive"))
    )
    (net (code "111") (name "Net-(Q9-B)") (class "Default")
      (node (ref "C50") (pin "1") (pinfunction "1_1") (pintype "passive"))
      (node (ref "Q9") (pin "2") (pinfunction "B_2") (pintype "passive"))
      (node (ref "R63") (pin "1") (pinfunction "1_1") (pintype "passive"))
    )
    (net (code "112") (name "Net-(Q9-E)") (class "Default")
      (node (ref "C48") (pin "2") (pinfunction "2_2") (pintype "passive"))
      (node (ref "C49") (pin "1") (pinfunction "1_1") (pintype "passive"))
      (node (ref "Q9") (pin "3") (pinfunction "E_3") (pintype "passive"))
      (node (ref "R93") (pin "2") (pinfunction "2_2") (pintype "passive"))
    )
    (net (code "113") (name "Net-(Q10-B)") (class "Default")
      (node (ref "C54") (pin "+") (pinfunction "+_+") (pintype "passive"))
      (node (ref "D14") (pin "A") (pinfunction "A_A") (pintype "passive"))
      (node (ref "Q10") (pin "2") (pinfunction "B_2") (pintype "passive"))
      (node (ref "R89") (pin "2") (pinfunction "2_2") (pintype "passive"))
    )
    (net (code "114") (name "Net-(Q10-E)") (class "Default")
      (node (ref "Q10") (pin "3") (pinfunction "E_3") (pintype "passive"))
      (node (ref "R72") (pin "2") (pinfunction "2_2") (pintype "passive"))
      (node (ref "R73") (pin "2") (pinfunction "2_2") (pintype "passive"))
      (node (ref "R85") (pin "2") (pinfunction "2_2") (pintype "passive"))
    )
    (net (code "115") (name "Net-(Q11-B)") (class "Default")
      (node (ref "Q11") (pin "2") (pinfunction "B_2") (pintype "passive"))
      (node (ref "R69") (pin "1") (pinfunction "1_1") (pintype "passive"))
    )
    (net (code "116") (name "Net-(Q11-C)") (class "Default")
      (node (ref "Q11") (pin "1") (pinfunction "C_1") (pintype "passive"))
      (node (ref "R70") (pin "2") (pinfunction "2_2") (pintype "passive"))
      (node (ref "R73") (pin "1") (pinfunction "1_1") (pintype "passive"))
    )
    (net (code "117") (name "Net-(Q12-B)") (class "Default")
      (node (ref "Q12") (pin "2") (pinfunction "B_2") (pintype "passive"))
      (node (ref "R71") (pin "1") (pinfunction "1_1") (pintype "passive"))
    )
    (net (code "118") (name "Net-(Q12-C)") (class "Default")
      (node (ref "Q12") (pin "1") (pinfunction "C_1") (pintype "passive"))
      (node (ref "R72") (pin "1") (pinfunction "1_1") (pintype "passive"))
      (node (ref "R74") (pin "2") (pinfunction "2_2") (pintype "passive"))
    )
    (net (code "119") (name "Net-(Q13-B)") (class "Default")
      (node (ref "C57") (pin "1") (pinfunction "1_1") (pintype "passive"))
      (node (ref "Q13") (pin "2") (pinfunction "B_2") (pintype "passive"))
      (node (ref "R82") (pin "2") (pinfunction "2_2") (pintype "passive"))
    )
    (net (code "120") (name "Net-(Q13-C)") (class "Default")
      (node (ref "C55") (pin "+") (pinfunction "+_+") (pintype "passive"))
      (node (ref "D16") (pin "C") (pinfunction "C_C") (pintype "passive"))
      (node (ref "D17") (pin "A") (pinfunction "A_A") (pintype "passive"))
      (node (ref "Q13") (pin "1") (pinfunction "C_1") (pintype "passive"))
      (node (ref "R79") (pin "1") (pinfunction "1_1") (pintype "passive"))
    )
    (net (code "121") (name "Net-(Q14-B)") (class "Default")
      (node (ref "Q14") (pin "2") (pinfunction "B_2") (pintype "passive"))
      (node (ref "R88") (pin "1") (pinfunction "1_1") (pintype "passive"))
    )
    (net (code "122") (name "Net-(Q15-B)") (class "Default")
      (node (ref "C52") (pin "+") (pinfunction "+_+") (pintype "passive"))
      (node (ref "Q15") (pin "2") (pinfunction "B_2") (pintype "passive"))
      (node (ref "R91") (pin "1") (pinfunction "1_1") (pintype "passive"))
      (node (ref "R94") (pin "1") (pinfunction "1_1") (pintype "passive"))
      (node (ref "R95") (pin "2") (pinfunction "2_2") (pintype "passive"))
    )
    (net (code "123") (name "Net-(R23-Pad2)") (class "Default")
      (node (ref "R23") (pin "2") (pinfunction "2_2") (pintype "passive"))
      (node (ref "R24") (pin "2") (pinfunction "2_2") (pintype "passive"))
      (node (ref "TONE") (pin "3") (pinfunction "3_3") (pintype "passive"))
    )
    (net (code "124") (name "OUT") (class "Default")
      (node (ref "R27") (pin "2") (pinfunction "2_2") (pintype "passive"))
    )
    (net (code "125") (name "VA") (class "Default")
      (node (ref "C43") (pin "+") (pinfunction "+_+") (pintype "passive"))
      (node (ref "IC5") (pin "14") (pinfunction "VDD_14") (pintype "power_in"))
      (node (ref "IC6") (pin "3") (pinfunction "VO_3") (pintype "passive"))
      (node (ref "IC7") (pin "16") (pinfunction "VDD_16") (pintype "power_in"))
    )
    (net (code "126") (name "VB") (class "Default")
      (node (ref "C19") (pin "+") (pinfunction "+_+") (pintype "passive"))
      (node (ref "Q8") (pin "1") (pinfunction "D_1") (pintype "passive"))
      (node (ref "R15") (pin "1") (pinfunction "1_1") (pintype "passive"))
      (node (ref "R20") (pin "1") (pinfunction "1_1") (pintype "passive"))
      (node (ref "R30") (pin "1") (pinfunction "1_1") (pintype "passive"))
      (node (ref "R32") (pin "1") (pinfunction "1_1") (pintype "passive"))
      (node (ref "R33") (pin "2") (pinfunction "2_2") (pintype "passive"))
      (node (ref "R34") (pin "2") (pinfunction "2_2") (pintype "passive"))
      (node (ref "R35") (pin "1") (pinfunction "1_1") (pintype "passive"))
      (node (ref "R65") (pin "1") (pinfunction "1_1") (pintype "passive"))
    )
    (net (code "127") (name "unconnected-(IC7A-DEMO-Pad10)") (class "Default")
      (node (ref "IC7") (pin "10") (pinfunction "DEMO_10") (pintype "output"))
    )
    (net (code "128") (name "unconnected-(IC7A-PC1-Pad2)") (class "Default")
      (node (ref "IC7") (pin "2") (pinfunction "PC1_2") (pintype "output"))
    )
    (net (code "129") (name "unconnected-(IC7A-PP-Pad1)") (class "Default")
      (node (ref "IC7") (pin "1") (pinfunction "PP_1") (pintype "output"))
    )
    (net (code "130") (name "unconnected-(IC7A-R2-Pad12)") (class "Default")
      (node (ref "IC7") (pin "12") (pinfunction "R2_12") (pintype "input"))
    )
    (net (code "131") (name "unconnected-(IC7A-ZEN-Pad15)") (class "Default")
      (node (ref "IC7") (pin "15") (pinfunction "ZEN_15") (pintype "input"))
    )
  )
)
